# backplane_v1_1-smd.net
KiCad netlist of a schematic drawn in EAGLE
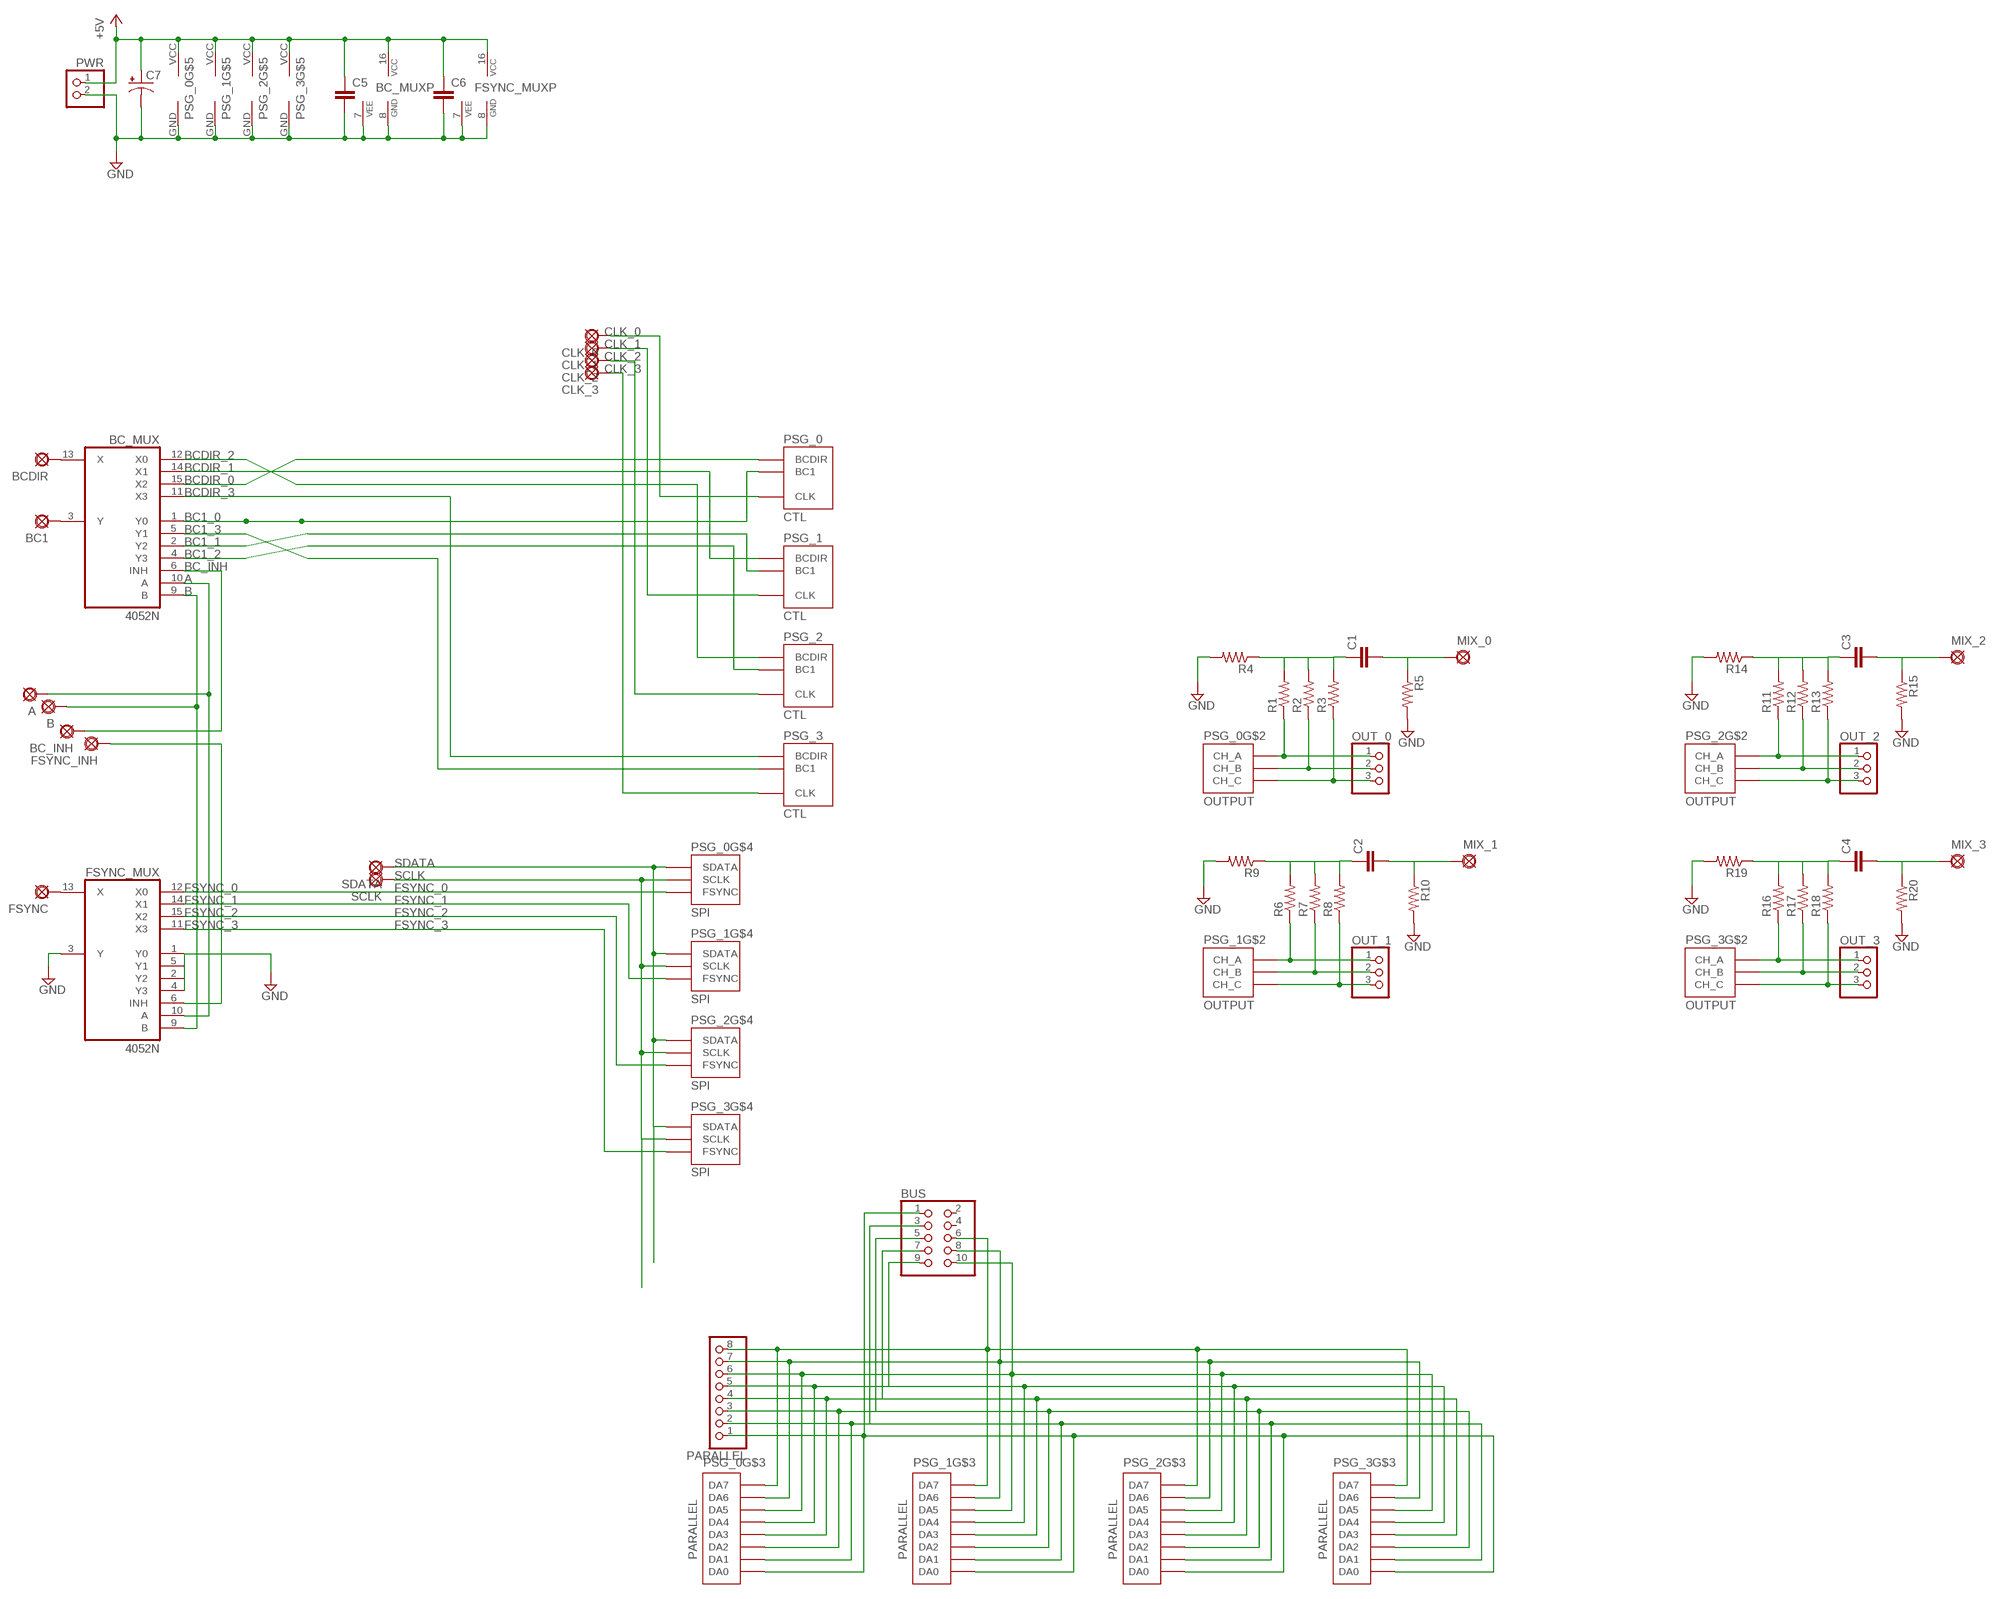
[diagram p0: schematic, sheet 1]

(export (version "E")
  (design (tool "Eeschema 10.0.6"))
  (components
    (comp (ref "A")
      (value "PAD")
      (footprint "eagle-import:SQUARE")
      (libsource (lib "eagle-import") (part "PAD"))
    )
    (comp (ref "B")
      (value "PAD")
      (footprint "eagle-import:SQUARE")
      (libsource (lib "eagle-import") (part "PAD"))
    )
    (comp (ref "BC1")
      (value "PAD")
      (footprint "eagle-import:SQUARE")
      (libsource (lib "eagle-import") (part "PAD"))
    )
    (comp (ref "BCDIR")
      (value "PAD")
      (footprint "eagle-import:SQUARE")
      (libsource (lib "eagle-import") (part "PAD"))
    )
    (comp (ref "BC_INH")
      (value "PAD")
      (footprint "eagle-import:SQUARE")
      (libsource (lib "eagle-import") (part "PAD"))
    )
    (comp (ref "BC_MUX")
      (value "4052N")
      (footprint "eagle-import:DIL16")
      (libsource (lib "eagle-import") (part "4052N"))
    )
    (comp (ref "BUS")
      (value "PINHD-2X5IDC")
      (footprint "eagle-import:10PIN_IDC")
      (libsource (lib "eagle-import") (part "PINHD-2X5IDC"))
    )
    (comp (ref "C1")
      (value "070X0302")
      (footprint "eagle-import:070X030")
      (libsource (lib "eagle-import") (part "070X0302"))
    )
    (comp (ref "C2")
      (value "070X0302")
      (footprint "eagle-import:070X030")
      (libsource (lib "eagle-import") (part "070X0302"))
    )
    (comp (ref "C3")
      (value "070X0302")
      (footprint "eagle-import:070X030")
      (libsource (lib "eagle-import") (part "070X0302"))
    )
    (comp (ref "C4")
      (value "070X0302")
      (footprint "eagle-import:070X030")
      (libsource (lib "eagle-import") (part "070X0302"))
    )
    (comp (ref "C5")
      (value "050X030_0251")
      (footprint "eagle-import:050X030_025")
      (libsource (lib "eagle-import") (part "050X030_0251"))
    )
    (comp (ref "C6")
      (value "050X030_0251")
      (footprint "eagle-import:050X030_025")
      (libsource (lib "eagle-import") (part "050X030_0251"))
    )
    (comp (ref "C7")
      (value "0631")
      (footprint "eagle-import:063_025")
      (libsource (lib "eagle-import") (part "0631"))
    )
    (comp (ref "CLK_0")
      (value "PAD")
      (footprint "eagle-import:SQUARE")
      (libsource (lib "eagle-import") (part "PAD"))
    )
    (comp (ref "CLK_1")
      (value "PAD")
      (footprint "eagle-import:SQUARE")
      (libsource (lib "eagle-import") (part "PAD"))
    )
    (comp (ref "CLK_2")
      (value "PAD")
      (footprint "eagle-import:SQUARE")
      (libsource (lib "eagle-import") (part "PAD"))
    )
    (comp (ref "CLK_3")
      (value "PAD")
      (footprint "eagle-import:SQUARE")
      (libsource (lib "eagle-import") (part "PAD"))
    )
    (comp (ref "FSYNC")
      (value "PAD")
      (footprint "eagle-import:SQUARE")
      (libsource (lib "eagle-import") (part "PAD"))
    )
    (comp (ref "FSYNC_INH")
      (value "PAD")
      (footprint "eagle-import:SQUARE")
      (libsource (lib "eagle-import") (part "PAD"))
    )
    (comp (ref "FSYNC_MUX")
      (value "4052N")
      (footprint "eagle-import:DIL16")
      (libsource (lib "eagle-import") (part "4052N"))
    )
    (comp (ref "MIX_0")
      (value "PAD")
      (footprint "eagle-import:SQUARE")
      (libsource (lib "eagle-import") (part "PAD"))
    )
    (comp (ref "MIX_1")
      (value "PAD")
      (footprint "eagle-import:SQUARE")
      (libsource (lib "eagle-import") (part "PAD"))
    )
    (comp (ref "MIX_2")
      (value "PAD")
      (footprint "eagle-import:SQUARE")
      (libsource (lib "eagle-import") (part "PAD"))
    )
    (comp (ref "MIX_3")
      (value "PAD")
      (footprint "eagle-import:SQUARE")
      (libsource (lib "eagle-import") (part "PAD"))
    )
    (comp (ref "OUT_0")
      (value "PINHD-1X3")
      (footprint "eagle-import:1X03")
      (libsource (lib "eagle-import") (part "PINHD-1X3"))
    )
    (comp (ref "OUT_1")
      (value "PINHD-1X3")
      (footprint "eagle-import:1X03")
      (libsource (lib "eagle-import") (part "PINHD-1X3"))
    )
    (comp (ref "OUT_2")
      (value "PINHD-1X3")
      (footprint "eagle-import:1X03")
      (libsource (lib "eagle-import") (part "PINHD-1X3"))
    )
    (comp (ref "OUT_3")
      (value "PINHD-1X3")
      (footprint "eagle-import:1X03")
      (libsource (lib "eagle-import") (part "PINHD-1X3"))
    )
    (comp (ref "PARALLEL")
      (value "PINHD-1X8")
      (footprint "eagle-import:1X08")
      (libsource (lib "eagle-import") (part "PINHD-1X8"))
    )
    (comp (ref "PSG_0")
      (value "PSG_DAUGHTER")
      (footprint "eagle-import:PSG_DAUGHTER")
      (libsource (lib "eagle-import") (part "PSG_DAUGHTER"))
    )
    (comp (ref "PSG_1")
      (value "PSG_DAUGHTER")
      (footprint "eagle-import:PSG_DAUGHTER")
      (libsource (lib "eagle-import") (part "PSG_DAUGHTER"))
    )
    (comp (ref "PSG_2")
      (value "PSG_DAUGHTER")
      (footprint "eagle-import:PSG_DAUGHTER")
      (libsource (lib "eagle-import") (part "PSG_DAUGHTER"))
    )
    (comp (ref "PSG_3")
      (value "PSG_DAUGHTER")
      (footprint "eagle-import:PSG_DAUGHTER")
      (libsource (lib "eagle-import") (part "PSG_DAUGHTER"))
    )
    (comp (ref "PWR")
      (value "PINHD-1X2")
      (footprint "eagle-import:1X02")
      (libsource (lib "eagle-import") (part "PINHD-1X2"))
    )
    (comp (ref "R1")
      (value "6MM.3")
      (footprint "eagle-import:R0207_3")
      (libsource (lib "eagle-import") (part "6MM.3"))
    )
    (comp (ref "R2")
      (value "6MM.3")
      (footprint "eagle-import:R0207_3")
      (libsource (lib "eagle-import") (part "6MM.3"))
    )
    (comp (ref "R3")
      (value "6MM.3")
      (footprint "eagle-import:R0207_3")
      (libsource (lib "eagle-import") (part "6MM.3"))
    )
    (comp (ref "R4")
      (value "6MM.3")
      (footprint "eagle-import:R0207_3")
      (libsource (lib "eagle-import") (part "6MM.3"))
    )
    (comp (ref "R5")
      (value "6MM.3")
      (footprint "eagle-import:R0207_3")
      (libsource (lib "eagle-import") (part "6MM.3"))
    )
    (comp (ref "R6")
      (value "6MM.3")
      (footprint "eagle-import:R0207_3")
      (libsource (lib "eagle-import") (part "6MM.3"))
    )
    (comp (ref "R7")
      (value "6MM.3")
      (footprint "eagle-import:R0207_3")
      (libsource (lib "eagle-import") (part "6MM.3"))
    )
    (comp (ref "R8")
      (value "6MM.3")
      (footprint "eagle-import:R0207_3")
      (libsource (lib "eagle-import") (part "6MM.3"))
    )
    (comp (ref "R9")
      (value "6MM.3")
      (footprint "eagle-import:R0207_3")
      (libsource (lib "eagle-import") (part "6MM.3"))
    )
    (comp (ref "R10")
      (value "6MM.3")
      (footprint "eagle-import:R0207_3")
      (libsource (lib "eagle-import") (part "6MM.3"))
    )
    (comp (ref "R11")
      (value "6MM.3")
      (footprint "eagle-import:R0207_3")
      (libsource (lib "eagle-import") (part "6MM.3"))
    )
    (comp (ref "R12")
      (value "6MM.3")
      (footprint "eagle-import:R0207_3")
      (libsource (lib "eagle-import") (part "6MM.3"))
    )
    (comp (ref "R13")
      (value "6MM.3")
      (footprint "eagle-import:R0207_3")
      (libsource (lib "eagle-import") (part "6MM.3"))
    )
    (comp (ref "R14")
      (value "6MM.3")
      (footprint "eagle-import:R0207_3")
      (libsource (lib "eagle-import") (part "6MM.3"))
    )
    (comp (ref "R15")
      (value "6MM.3")
      (footprint "eagle-import:R0207_3")
      (libsource (lib "eagle-import") (part "6MM.3"))
    )
    (comp (ref "R16")
      (value "6MM.3")
      (footprint "eagle-import:R0207_3")
      (libsource (lib "eagle-import") (part "6MM.3"))
    )
    (comp (ref "R17")
      (value "6MM.3")
      (footprint "eagle-import:R0207_3")
      (libsource (lib "eagle-import") (part "6MM.3"))
    )
    (comp (ref "R18")
      (value "6MM.3")
      (footprint "eagle-import:R0207_3")
      (libsource (lib "eagle-import") (part "6MM.3"))
    )
    (comp (ref "R19")
      (value "6MM.3")
      (footprint "eagle-import:R0207_3")
      (libsource (lib "eagle-import") (part "6MM.3"))
    )
    (comp (ref "R20")
      (value "6MM.3")
      (footprint "eagle-import:R0207_3")
      (libsource (lib "eagle-import") (part "6MM.3"))
    )
    (comp (ref "SCLK")
      (value "PAD")
      (footprint "eagle-import:SQUARE")
      (libsource (lib "eagle-import") (part "PAD"))
    )
    (comp (ref "SDATA")
      (value "PAD")
      (footprint "eagle-import:SQUARE")
      (libsource (lib "eagle-import") (part "PAD"))
    )
  )
  (nets
    (net (code "1") (name "+5V") (class "Default")
      (node (ref "BC_MUX") (pin "16") (pinfunction "VCC_16") (pintype "power_in"))
      (node (ref "C5") (pin "1") (pinfunction "1_1") (pintype "passive"))
      (node (ref "C6") (pin "1") (pinfunction "1_1") (pintype "passive"))
      (node (ref "C7") (pin "+") (pinfunction "+_+") (pintype "passive"))
      (node (ref "FSYNC_MUX") (pin "16") (pinfunction "VCC_16") (pintype "power_in"))
      (node (ref "PSG_0") (pin "VCC") (pinfunction "VCC_VCC") (pintype "power_in"))
      (node (ref "PSG_1") (pin "VCC") (pinfunction "VCC_VCC") (pintype "power_in"))
      (node (ref "PSG_2") (pin "VCC") (pinfunction "VCC_VCC") (pintype "power_in"))
      (node (ref "PSG_3") (pin "VCC") (pinfunction "VCC_VCC") (pintype "power_in"))
      (node (ref "PWR") (pin "1") (pinfunction "1_1") (pintype "passive"))
    )
    (net (code "2") (name "/A") (class "Default")
      (node (ref "A") (pin "1") (pinfunction "PAD_1") (pintype "passive"))
      (node (ref "BC_MUX") (pin "10") (pinfunction "A_10") (pintype "input"))
      (node (ref "FSYNC_MUX") (pin "10") (pinfunction "A_10") (pintype "input"))
    )
    (net (code "3") (name "/B") (class "Default")
      (node (ref "B") (pin "1") (pinfunction "PAD_1") (pintype "passive"))
      (node (ref "BC_MUX") (pin "9") (pinfunction "B_9") (pintype "input"))
      (node (ref "FSYNC_MUX") (pin "9") (pinfunction "B_9") (pintype "input"))
    )
    (net (code "4") (name "/BC1_0") (class "Default")
      (node (ref "BC_MUX") (pin "1") (pinfunction "Y0_1") (pintype "bidirectional"))
      (node (ref "PSG_0") (pin "BC1") (pinfunction "BC1_BC1") (pintype "input"))
    )
    (net (code "5") (name "/BC1_1") (class "Default")
      (node (ref "BC_MUX") (pin "2") (pinfunction "Y2_2") (pintype "bidirectional"))
      (node (ref "PSG_1") (pin "BC1") (pinfunction "BC1_BC1") (pintype "input"))
    )
    (net (code "6") (name "/BC1_2") (class "Default")
      (node (ref "BC_MUX") (pin "4") (pinfunction "Y3_4") (pintype "bidirectional"))
      (node (ref "PSG_2") (pin "BC1") (pinfunction "BC1_BC1") (pintype "input"))
    )
    (net (code "7") (name "/BC1_3") (class "Default")
      (node (ref "BC_MUX") (pin "5") (pinfunction "Y1_5") (pintype "bidirectional"))
      (node (ref "PSG_3") (pin "BC1") (pinfunction "BC1_BC1") (pintype "input"))
    )
    (net (code "8") (name "/BCDIR_0") (class "Default")
      (node (ref "BC_MUX") (pin "15") (pinfunction "X2_15") (pintype "bidirectional"))
      (node (ref "PSG_0") (pin "BCDIR") (pinfunction "BCDIR_BCDIR") (pintype "input"))
    )
    (net (code "9") (name "/BCDIR_1") (class "Default")
      (node (ref "BC_MUX") (pin "14") (pinfunction "X1_14") (pintype "bidirectional"))
      (node (ref "PSG_1") (pin "BCDIR") (pinfunction "BCDIR_BCDIR") (pintype "input"))
    )
    (net (code "10") (name "/BCDIR_2") (class "Default")
      (node (ref "BC_MUX") (pin "12") (pinfunction "X0_12") (pintype "bidirectional"))
      (node (ref "PSG_2") (pin "BCDIR") (pinfunction "BCDIR_BCDIR") (pintype "input"))
    )
    (net (code "11") (name "/BCDIR_3") (class "Default")
      (node (ref "BC_MUX") (pin "11") (pinfunction "X3_11") (pintype "bidirectional"))
      (node (ref "PSG_3") (pin "BCDIR") (pinfunction "BCDIR_BCDIR") (pintype "input"))
    )
    (net (code "12") (name "/BC_INH") (class "Default")
      (node (ref "BC_INH") (pin "1") (pinfunction "PAD_1") (pintype "passive"))
      (node (ref "BC_MUX") (pin "6") (pinfunction "INH_6") (pintype "input"))
    )
    (net (code "13") (name "/CLK_0") (class "Default")
      (node (ref "CLK_0") (pin "1") (pinfunction "PAD_1") (pintype "passive"))
      (node (ref "PSG_0") (pin "CLK") (pinfunction "CLK_CLK") (pintype "input"))
    )
    (net (code "14") (name "/CLK_1") (class "Default")
      (node (ref "CLK_1") (pin "1") (pinfunction "PAD_1") (pintype "passive"))
      (node (ref "PSG_1") (pin "CLK") (pinfunction "CLK_CLK") (pintype "input"))
    )
    (net (code "15") (name "/CLK_2") (class "Default")
      (node (ref "CLK_2") (pin "1") (pinfunction "PAD_1") (pintype "passive"))
      (node (ref "PSG_2") (pin "CLK") (pinfunction "CLK_CLK") (pintype "input"))
    )
    (net (code "16") (name "/CLK_3") (class "Default")
      (node (ref "CLK_3") (pin "1") (pinfunction "PAD_1") (pintype "passive"))
      (node (ref "PSG_3") (pin "CLK") (pinfunction "CLK_CLK") (pintype "input"))
    )
    (net (code "17") (name "/FSYNC_0") (class "Default")
      (node (ref "FSYNC_MUX") (pin "12") (pinfunction "X0_12") (pintype "bidirectional"))
      (node (ref "PSG_0") (pin "FSYNC") (pinfunction "FSYNC_FSYNC") (pintype "input"))
    )
    (net (code "18") (name "/FSYNC_1") (class "Default")
      (node (ref "FSYNC_MUX") (pin "14") (pinfunction "X1_14") (pintype "bidirectional"))
      (node (ref "PSG_1") (pin "FSYNC") (pinfunction "FSYNC_FSYNC") (pintype "input"))
    )
    (net (code "19") (name "/FSYNC_2") (class "Default")
      (node (ref "FSYNC_MUX") (pin "15") (pinfunction "X2_15") (pintype "bidirectional"))
      (node (ref "PSG_2") (pin "FSYNC") (pinfunction "FSYNC_FSYNC") (pintype "input"))
    )
    (net (code "20") (name "/FSYNC_3") (class "Default")
      (node (ref "FSYNC_MUX") (pin "11") (pinfunction "X3_11") (pintype "bidirectional"))
      (node (ref "PSG_3") (pin "FSYNC") (pinfunction "FSYNC_FSYNC") (pintype "input"))
    )
    (net (code "21") (name "/SCLK") (class "Default")
      (node (ref "PSG_0") (pin "SCLK") (pinfunction "SCLK_SCLK") (pintype "input"))
      (node (ref "PSG_1") (pin "SCLK") (pinfunction "SCLK_SCLK") (pintype "input"))
      (node (ref "PSG_2") (pin "SCLK") (pinfunction "SCLK_SCLK") (pintype "input"))
      (node (ref "PSG_3") (pin "SCLK") (pinfunction "SCLK_SCLK") (pintype "input"))
      (node (ref "SCLK") (pin "1") (pinfunction "PAD_1") (pintype "passive"))
    )
    (net (code "22") (name "/SDATA") (class "Default")
      (node (ref "PSG_0") (pin "SDATA") (pinfunction "SDATA_SDATA") (pintype "bidirectional"))
      (node (ref "PSG_1") (pin "SDATA") (pinfunction "SDATA_SDATA") (pintype "bidirectional"))
      (node (ref "PSG_2") (pin "SDATA") (pinfunction "SDATA_SDATA") (pintype "bidirectional"))
      (node (ref "PSG_3") (pin "SDATA") (pinfunction "SDATA_SDATA") (pintype "bidirectional"))
      (node (ref "SDATA") (pin "1") (pinfunction "PAD_1") (pintype "passive"))
    )
    (net (code "23") (name "GND") (class "Default")
      (node (ref "BC_MUX") (pin "7") (pinfunction "VEE_7") (pintype "power_in"))
      (node (ref "BC_MUX") (pin "8") (pinfunction "GND_8") (pintype "power_in"))
      (node (ref "C5") (pin "2") (pinfunction "2_2") (pintype "passive"))
      (node (ref "C6") (pin "2") (pinfunction "2_2") (pintype "passive"))
      (node (ref "C7") (pin "-") (pinfunction "-_-") (pintype "passive"))
      (node (ref "FSYNC_MUX") (pin "1") (pinfunction "Y0_1") (pintype "bidirectional"))
      (node (ref "FSYNC_MUX") (pin "2") (pinfunction "Y2_2") (pintype "bidirectional"))
      (node (ref "FSYNC_MUX") (pin "3") (pinfunction "Y_3") (pintype "bidirectional"))
      (node (ref "FSYNC_MUX") (pin "4") (pinfunction "Y3_4") (pintype "bidirectional"))
      (node (ref "FSYNC_MUX") (pin "5") (pinfunction "Y1_5") (pintype "bidirectional"))
      (node (ref "FSYNC_MUX") (pin "7") (pinfunction "VEE_7") (pintype "power_in"))
      (node (ref "FSYNC_MUX") (pin "8") (pinfunction "GND_8") (pintype "power_in"))
      (node (ref "PSG_0") (pin "GND") (pinfunction "GND_GND") (pintype "power_in"))
      (node (ref "PSG_1") (pin "GND") (pinfunction "GND_GND") (pintype "power_in"))
      (node (ref "PSG_2") (pin "GND") (pinfunction "GND_GND") (pintype "power_in"))
      (node (ref "PSG_3") (pin "GND") (pinfunction "GND_GND") (pintype "power_in"))
      (node (ref "PWR") (pin "2") (pinfunction "2_2") (pintype "passive"))
      (node (ref "R10") (pin "2") (pinfunction "2_2") (pintype "passive"))
      (node (ref "R14") (pin "2") (pinfunction "2_2") (pintype "passive"))
      (node (ref "R15") (pin "2") (pinfunction "2_2") (pintype "passive"))
      (node (ref "R19") (pin "2") (pinfunction "2_2") (pintype "passive"))
      (node (ref "R20") (pin "2") (pinfunction "2_2") (pintype "passive"))
      (node (ref "R4") (pin "2") (pinfunction "2_2") (pintype "passive"))
      (node (ref "R5") (pin "2") (pinfunction "2_2") (pintype "passive"))
      (node (ref "R9") (pin "2") (pinfunction "2_2") (pintype "passive"))
    )
    (net (code "24") (name "Net-(BC1-PAD)") (class "Default")
      (node (ref "BC1") (pin "1") (pinfunction "PAD_1") (pintype "passive"))
      (node (ref "BC_MUX") (pin "3") (pinfunction "Y_3") (pintype "bidirectional"))
    )
    (net (code "25") (name "Net-(BCDIR-PAD)") (class "Default")
      (node (ref "BCDIR") (pin "1") (pinfunction "PAD_1") (pintype "passive"))
      (node (ref "BC_MUX") (pin "13") (pinfunction "X_13") (pintype "bidirectional"))
    )
    (net (code "26") (name "Net-(BUS-Pad1)") (class "Default")
      (node (ref "BUS") (pin "1") (pinfunction "1_1") (pintype "passive"))
      (node (ref "PARALLEL") (pin "1") (pinfunction "1_1") (pintype "passive"))
      (node (ref "PSG_0") (pin "DA0") (pinfunction "DA0_DA0") (pintype "bidirectional"))
      (node (ref "PSG_1") (pin "DA0") (pinfunction "DA0_DA0") (pintype "bidirectional"))
      (node (ref "PSG_2") (pin "DA0") (pinfunction "DA0_DA0") (pintype "bidirectional"))
      (node (ref "PSG_3") (pin "DA0") (pinfunction "DA0_DA0") (pintype "bidirectional"))
    )
    (net (code "27") (name "Net-(BUS-Pad3)") (class "Default")
      (node (ref "BUS") (pin "3") (pinfunction "3_3") (pintype "passive"))
      (node (ref "PARALLEL") (pin "2") (pinfunction "2_2") (pintype "passive"))
      (node (ref "PSG_0") (pin "DA1") (pinfunction "DA1_DA1") (pintype "bidirectional"))
      (node (ref "PSG_1") (pin "DA1") (pinfunction "DA1_DA1") (pintype "bidirectional"))
      (node (ref "PSG_2") (pin "DA1") (pinfunction "DA1_DA1") (pintype "bidirectional"))
      (node (ref "PSG_3") (pin "DA1") (pinfunction "DA1_DA1") (pintype "bidirectional"))
    )
    (net (code "28") (name "Net-(BUS-Pad5)") (class "Default")
      (node (ref "BUS") (pin "5") (pinfunction "5_5") (pintype "passive"))
      (node (ref "PARALLEL") (pin "3") (pinfunction "3_3") (pintype "passive"))
      (node (ref "PSG_0") (pin "DA2") (pinfunction "DA2_DA2") (pintype "bidirectional"))
      (node (ref "PSG_1") (pin "DA2") (pinfunction "DA2_DA2") (pintype "bidirectional"))
      (node (ref "PSG_2") (pin "DA2") (pinfunction "DA2_DA2") (pintype "bidirectional"))
      (node (ref "PSG_3") (pin "DA2") (pinfunction "DA2_DA2") (pintype "bidirectional"))
    )
    (net (code "29") (name "Net-(BUS-Pad6)") (class "Default")
      (node (ref "BUS") (pin "6") (pinfunction "6_6") (pintype "passive"))
      (node (ref "PARALLEL") (pin "8") (pinfunction "8_8") (pintype "passive"))
      (node (ref "PSG_0") (pin "DA7") (pinfunction "DA7_DA7") (pintype "bidirectional"))
      (node (ref "PSG_1") (pin "DA7") (pinfunction "DA7_DA7") (pintype "bidirectional"))
      (node (ref "PSG_2") (pin "DA7") (pinfunction "DA7_DA7") (pintype "bidirectional"))
      (node (ref "PSG_3") (pin "DA7") (pinfunction "DA7_DA7") (pintype "bidirectional"))
    )
    (net (code "30") (name "Net-(BUS-Pad7)") (class "Default")
      (node (ref "BUS") (pin "7") (pinfunction "7_7") (pintype "passive"))
      (node (ref "PARALLEL") (pin "4") (pinfunction "4_4") (pintype "passive"))
      (node (ref "PSG_0") (pin "DA3") (pinfunction "DA3_DA3") (pintype "bidirectional"))
      (node (ref "PSG_1") (pin "DA3") (pinfunction "DA3_DA3") (pintype "bidirectional"))
      (node (ref "PSG_2") (pin "DA3") (pinfunction "DA3_DA3") (pintype "bidirectional"))
      (node (ref "PSG_3") (pin "DA3") (pinfunction "DA3_DA3") (pintype "bidirectional"))
    )
    (net (code "31") (name "Net-(BUS-Pad8)") (class "Default")
      (node (ref "BUS") (pin "8") (pinfunction "8_8") (pintype "passive"))
      (node (ref "PARALLEL") (pin "7") (pinfunction "7_7") (pintype "passive"))
      (node (ref "PSG_0") (pin "DA6") (pinfunction "DA6_DA6") (pintype "bidirectional"))
      (node (ref "PSG_1") (pin "DA6") (pinfunction "DA6_DA6") (pintype "bidirectional"))
      (node (ref "PSG_2") (pin "DA6") (pinfunction "DA6_DA6") (pintype "bidirectional"))
      (node (ref "PSG_3") (pin "DA6") (pinfunction "DA6_DA6") (pintype "bidirectional"))
    )
    (net (code "32") (name "Net-(BUS-Pad9)") (class "Default")
      (node (ref "BUS") (pin "9") (pinfunction "9_9") (pintype "passive"))
      (node (ref "PARALLEL") (pin "5") (pinfunction "5_5") (pintype "passive"))
      (node (ref "PSG_0") (pin "DA4") (pinfunction "DA4_DA4") (pintype "bidirectional"))
      (node (ref "PSG_1") (pin "DA4") (pinfunction "DA4_DA4") (pintype "bidirectional"))
      (node (ref "PSG_2") (pin "DA4") (pinfunction "DA4_DA4") (pintype "bidirectional"))
      (node (ref "PSG_3") (pin "DA4") (pinfunction "DA4_DA4") (pintype "bidirectional"))
    )
    (net (code "33") (name "Net-(BUS-Pad10)") (class "Default")
      (node (ref "BUS") (pin "10") (pinfunction "10_10") (pintype "passive"))
      (node (ref "PARALLEL") (pin "6") (pinfunction "6_6") (pintype "passive"))
      (node (ref "PSG_0") (pin "DA5") (pinfunction "DA5_DA5") (pintype "bidirectional"))
      (node (ref "PSG_1") (pin "DA5") (pinfunction "DA5_DA5") (pintype "bidirectional"))
      (node (ref "PSG_2") (pin "DA5") (pinfunction "DA5_DA5") (pintype "bidirectional"))
      (node (ref "PSG_3") (pin "DA5") (pinfunction "DA5_DA5") (pintype "bidirectional"))
    )
    (net (code "34") (name "Net-(C1-Pad1)") (class "Default")
      (node (ref "C1") (pin "1") (pinfunction "1_1") (pintype "passive"))
      (node (ref "R1") (pin "2") (pinfunction "2_2") (pintype "passive"))
      (node (ref "R2") (pin "2") (pinfunction "2_2") (pintype "passive"))
      (node (ref "R3") (pin "2") (pinfunction "2_2") (pintype "passive"))
      (node (ref "R4") (pin "1") (pinfunction "1_1") (pintype "passive"))
    )
    (net (code "35") (name "Net-(C2-Pad1)") (class "Default")
      (node (ref "C2") (pin "1") (pinfunction "1_1") (pintype "passive"))
      (node (ref "R6") (pin "2") (pinfunction "2_2") (pintype "passive"))
      (node (ref "R7") (pin "2") (pinfunction "2_2") (pintype "passive"))
      (node (ref "R8") (pin "2") (pinfunction "2_2") (pintype "passive"))
      (node (ref "R9") (pin "1") (pinfunction "1_1") (pintype "passive"))
    )
    (net (code "36") (name "Net-(C3-Pad1)") (class "Default")
      (node (ref "C3") (pin "1") (pinfunction "1_1") (pintype "passive"))
      (node (ref "R11") (pin "2") (pinfunction "2_2") (pintype "passive"))
      (node (ref "R12") (pin "2") (pinfunction "2_2") (pintype "passive"))
      (node (ref "R13") (pin "2") (pinfunction "2_2") (pintype "passive"))
      (node (ref "R14") (pin "1") (pinfunction "1_1") (pintype "passive"))
    )
    (net (code "37") (name "Net-(C4-Pad1)") (class "Default")
      (node (ref "C4") (pin "1") (pinfunction "1_1") (pintype "passive"))
      (node (ref "R16") (pin "2") (pinfunction "2_2") (pintype "passive"))
      (node (ref "R17") (pin "2") (pinfunction "2_2") (pintype "passive"))
      (node (ref "R18") (pin "2") (pinfunction "2_2") (pintype "passive"))
      (node (ref "R19") (pin "1") (pinfunction "1_1") (pintype "passive"))
    )
    (net (code "38") (name "Net-(FSYNC-PAD)") (class "Default")
      (node (ref "FSYNC") (pin "1") (pinfunction "PAD_1") (pintype "passive"))
      (node (ref "FSYNC_MUX") (pin "13") (pinfunction "X_13") (pintype "bidirectional"))
    )
    (net (code "39") (name "Net-(FSYNC_INH-PAD)") (class "Default")
      (node (ref "FSYNC_INH") (pin "1") (pinfunction "PAD_1") (pintype "passive"))
      (node (ref "FSYNC_MUX") (pin "6") (pinfunction "INH_6") (pintype "input"))
    )
    (net (code "40") (name "Net-(MIX_0-PAD)") (class "Default")
      (node (ref "C1") (pin "2") (pinfunction "2_2") (pintype "passive"))
      (node (ref "MIX_0") (pin "1") (pinfunction "PAD_1") (pintype "passive"))
      (node (ref "R5") (pin "1") (pinfunction "1_1") (pintype "passive"))
    )
    (net (code "41") (name "Net-(MIX_1-PAD)") (class "Default")
      (node (ref "C2") (pin "2") (pinfunction "2_2") (pintype "passive"))
      (node (ref "MIX_1") (pin "1") (pinfunction "PAD_1") (pintype "passive"))
      (node (ref "R10") (pin "1") (pinfunction "1_1") (pintype "passive"))
    )
    (net (code "42") (name "Net-(MIX_2-PAD)") (class "Default")
      (node (ref "C3") (pin "2") (pinfunction "2_2") (pintype "passive"))
      (node (ref "MIX_2") (pin "1") (pinfunction "PAD_1") (pintype "passive"))
      (node (ref "R15") (pin "1") (pinfunction "1_1") (pintype "passive"))
    )
    (net (code "43") (name "Net-(MIX_3-PAD)") (class "Default")
      (node (ref "C4") (pin "2") (pinfunction "2_2") (pintype "passive"))
      (node (ref "MIX_3") (pin "1") (pinfunction "PAD_1") (pintype "passive"))
      (node (ref "R20") (pin "1") (pinfunction "1_1") (pintype "passive"))
    )
    (net (code "44") (name "Net-(PSG_0B-CH_A)") (class "Default")
      (node (ref "OUT_0") (pin "1") (pinfunction "1_1") (pintype "passive"))
      (node (ref "PSG_0") (pin "OUT_A") (pinfunction "CH_A_OUT_A") (pintype "input"))
      (node (ref "R1") (pin "1") (pinfunction "1_1") (pintype "passive"))
    )
    (net (code "45") (name "Net-(PSG_0B-CH_B)") (class "Default")
      (node (ref "OUT_0") (pin "2") (pinfunction "2_2") (pintype "passive"))
      (node (ref "PSG_0") (pin "OUT_B") (pinfunction "CH_B_OUT_B") (pintype "input"))
      (node (ref "R2") (pin "1") (pinfunction "1_1") (pintype "passive"))
    )
    (net (code "46") (name "Net-(PSG_0B-CH_C)") (class "Default")
      (node (ref "OUT_0") (pin "3") (pinfunction "3_3") (pintype "passive"))
      (node (ref "PSG_0") (pin "OUT_C") (pinfunction "CH_C_OUT_C") (pintype "input"))
      (node (ref "R3") (pin "1") (pinfunction "1_1") (pintype "passive"))
    )
    (net (code "47") (name "Net-(PSG_1B-CH_A)") (class "Default")
      (node (ref "OUT_1") (pin "1") (pinfunction "1_1") (pintype "passive"))
      (node (ref "PSG_1") (pin "OUT_A") (pinfunction "CH_A_OUT_A") (pintype "input"))
      (node (ref "R6") (pin "1") (pinfunction "1_1") (pintype "passive"))
    )
    (net (code "48") (name "Net-(PSG_1B-CH_B)") (class "Default")
      (node (ref "OUT_1") (pin "2") (pinfunction "2_2") (pintype "passive"))
      (node (ref "PSG_1") (pin "OUT_B") (pinfunction "CH_B_OUT_B") (pintype "input"))
      (node (ref "R7") (pin "1") (pinfunction "1_1") (pintype "passive"))
    )
    (net (code "49") (name "Net-(PSG_1B-CH_C)") (class "Default")
      (node (ref "OUT_1") (pin "3") (pinfunction "3_3") (pintype "passive"))
      (node (ref "PSG_1") (pin "OUT_C") (pinfunction "CH_C_OUT_C") (pintype "input"))
      (node (ref "R8") (pin "1") (pinfunction "1_1") (pintype "passive"))
    )
    (net (code "50") (name "Net-(PSG_2B-CH_A)") (class "Default")
      (node (ref "OUT_2") (pin "1") (pinfunction "1_1") (pintype "passive"))
      (node (ref "PSG_2") (pin "OUT_A") (pinfunction "CH_A_OUT_A") (pintype "input"))
      (node (ref "R11") (pin "1") (pinfunction "1_1") (pintype "passive"))
    )
    (net (code "51") (name "Net-(PSG_2B-CH_B)") (class "Default")
      (node (ref "OUT_2") (pin "2") (pinfunction "2_2") (pintype "passive"))
      (node (ref "PSG_2") (pin "OUT_B") (pinfunction "CH_B_OUT_B") (pintype "input"))
      (node (ref "R12") (pin "1") (pinfunction "1_1") (pintype "passive"))
    )
    (net (code "52") (name "Net-(PSG_2B-CH_C)") (class "Default")
      (node (ref "OUT_2") (pin "3") (pinfunction "3_3") (pintype "passive"))
      (node (ref "PSG_2") (pin "OUT_C") (pinfunction "CH_C_OUT_C") (pintype "input"))
      (node (ref "R13") (pin "1") (pinfunction "1_1") (pintype "passive"))
    )
    (net (code "53") (name "Net-(PSG_3B-CH_A)") (class "Default")
      (node (ref "OUT_3") (pin "1") (pinfunction "1_1") (pintype "passive"))
      (node (ref "PSG_3") (pin "OUT_A") (pinfunction "CH_A_OUT_A") (pintype "input"))
      (node (ref "R16") (pin "1") (pinfunction "1_1") (pintype "passive"))
    )
    (net (code "54") (name "Net-(PSG_3B-CH_B)") (class "Default")
      (node (ref "OUT_3") (pin "2") (pinfunction "2_2") (pintype "passive"))
      (node (ref "PSG_3") (pin "OUT_B") (pinfunction "CH_B_OUT_B") (pintype "input"))
      (node (ref "R17") (pin "1") (pinfunction "1_1") (pintype "passive"))
    )
    (net (code "55") (name "Net-(PSG_3B-CH_C)") (class "Default")
      (node (ref "OUT_3") (pin "3") (pinfunction "3_3") (pintype "passive"))
      (node (ref "PSG_3") (pin "OUT_C") (pinfunction "CH_C_OUT_C") (pintype "input"))
      (node (ref "R18") (pin "1") (pinfunction "1_1") (pintype "passive"))
    )
    (net (code "56") (name "unconnected-(BUS-Pad2)") (class "Default")
      (node (ref "BUS") (pin "2") (pinfunction "2_2") (pintype "passive"))
    )
    (net (code "57") (name "unconnected-(BUS-Pad4)") (class "Default")
      (node (ref "BUS") (pin "4") (pinfunction "4_4") (pintype "passive"))
    )
  )
)
